# V2b.net
KiCad netlist of a schematic drawn in EAGLE
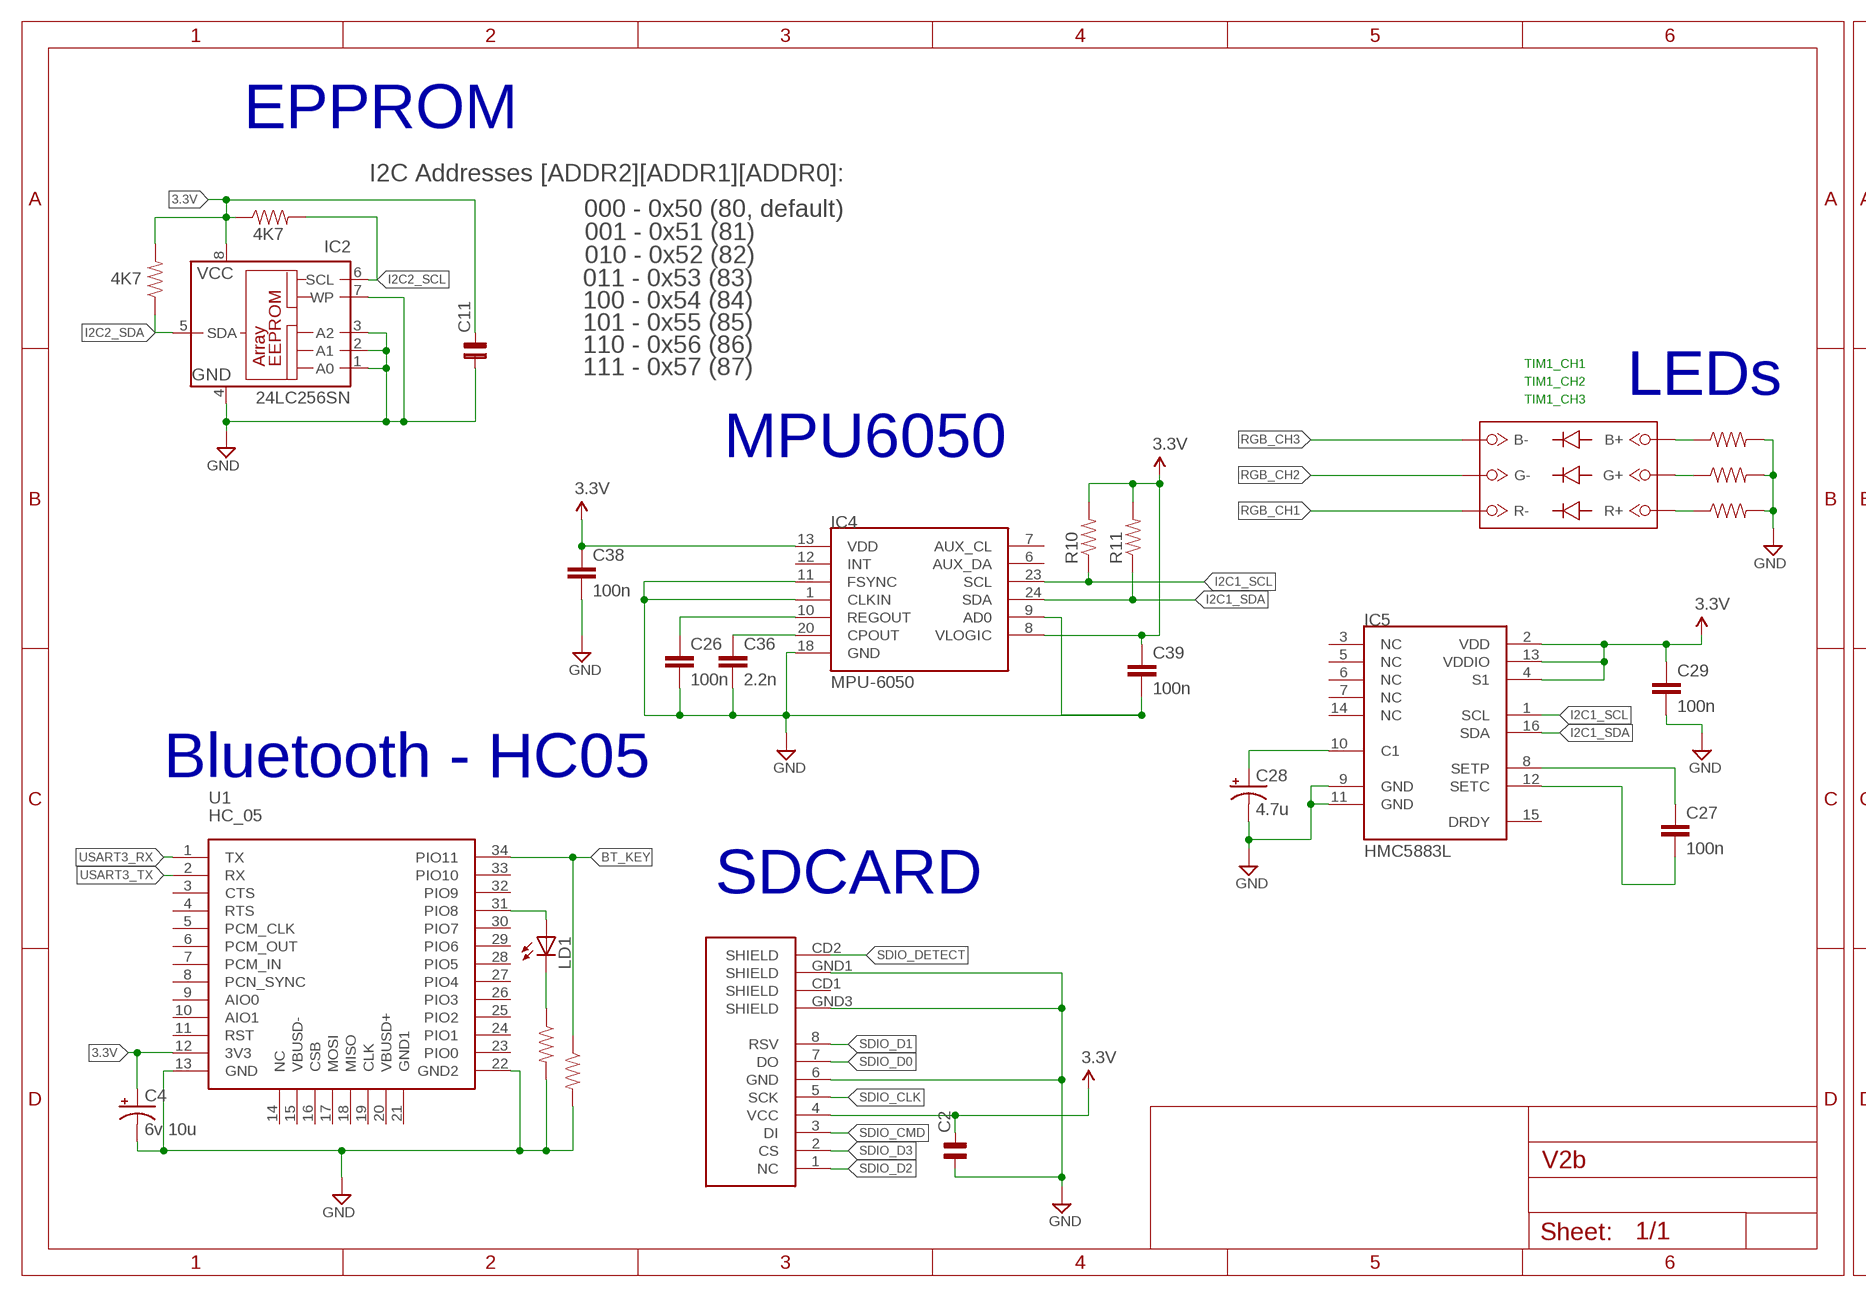
[diagram p0: schematic, sheet 1, part 1 of 2]
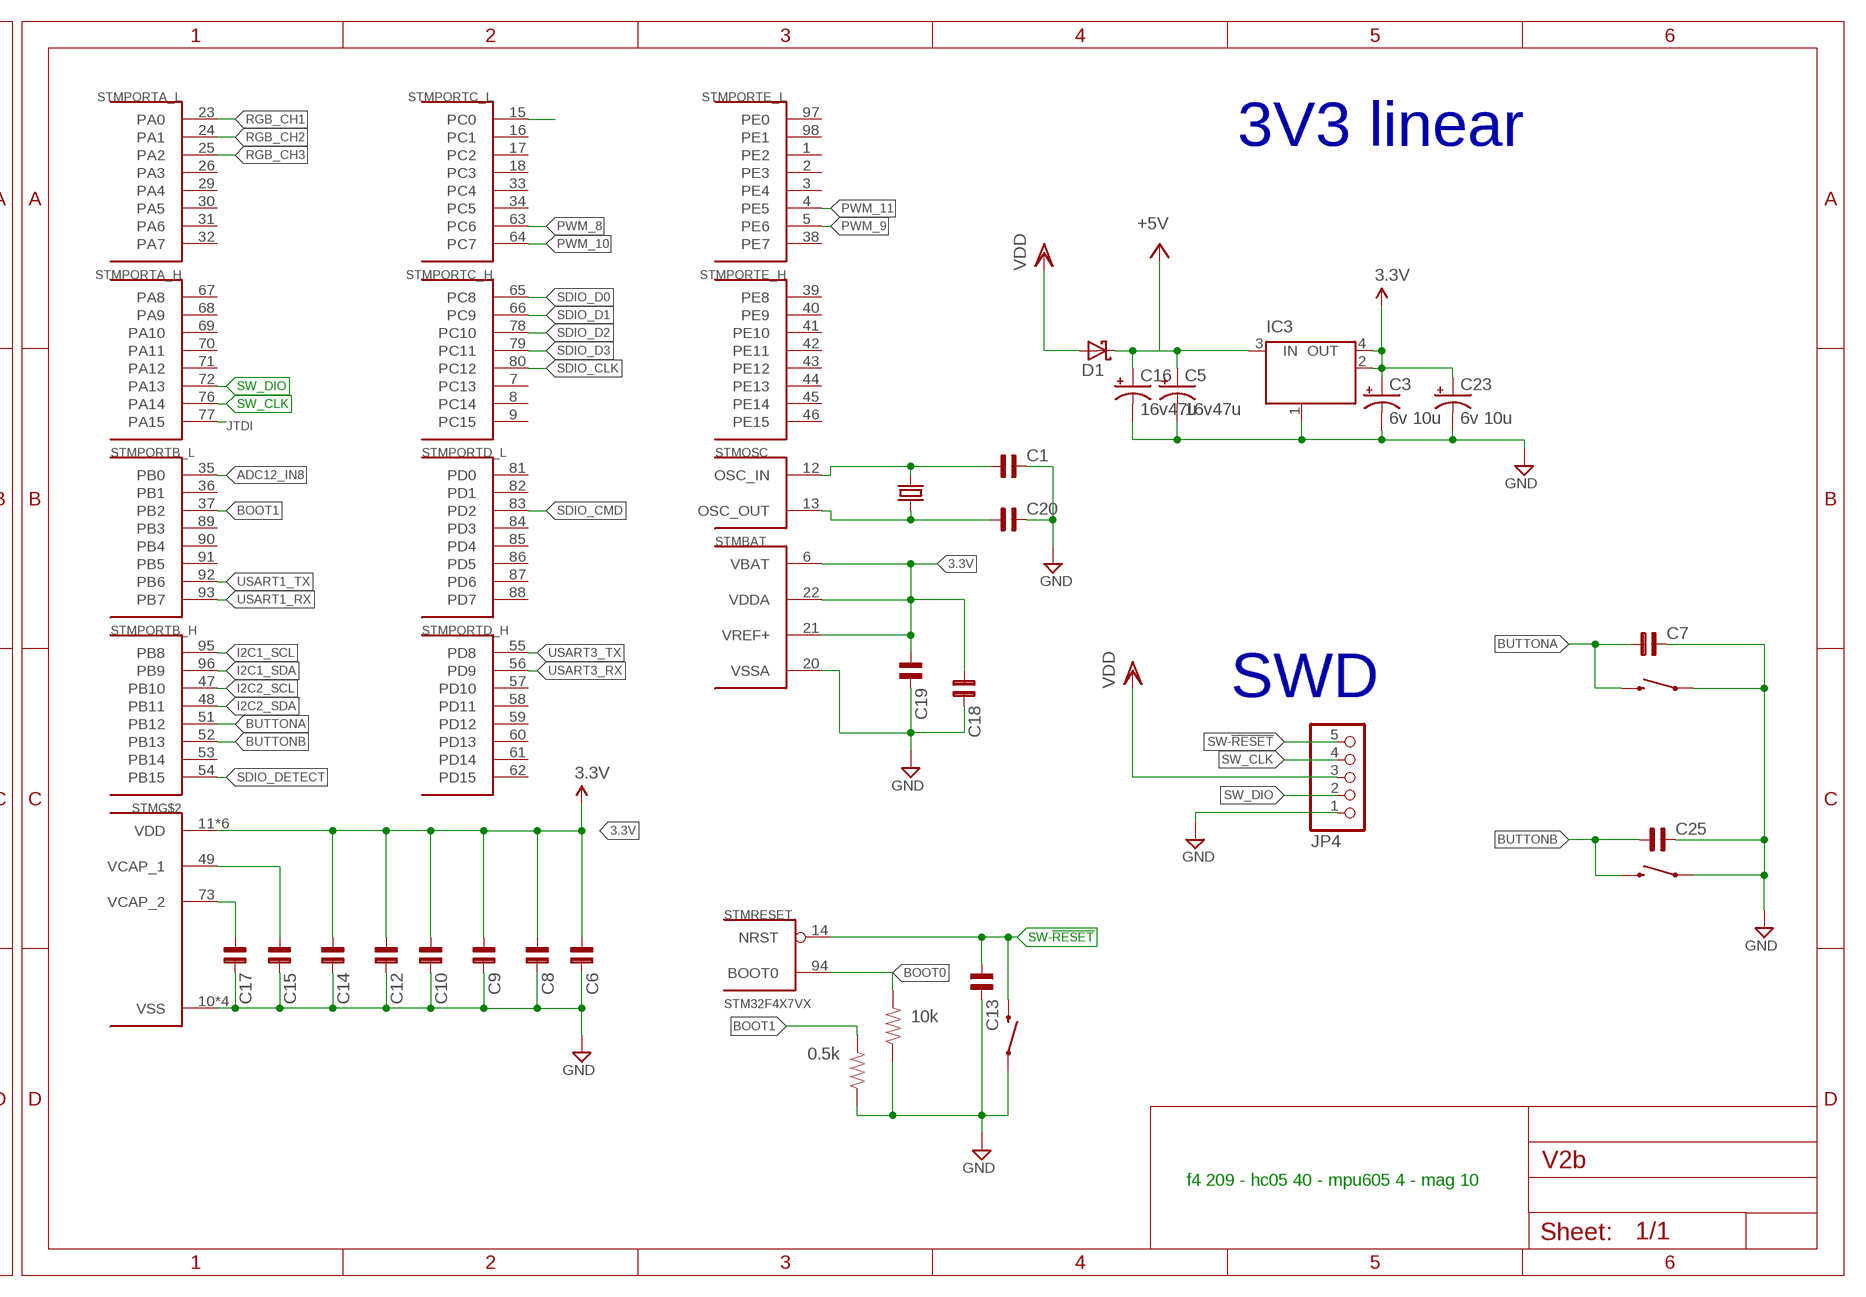
[diagram p1: schematic, sheet 1, part 2 of 2]

(export (version "E")
  (design (tool "Eeschema 10.0.6"))
  (components
    (comp (ref "C1")
      (value "C-NP-SMD-0603")
      (footprint "eagle-import:C-0603")
      (libsource (lib "eagle-import") (part "C-NP-SMD-0603"))
    )
    (comp (ref "C2")
      (value "C-NP-SMD-0603")
      (footprint "eagle-import:C-0603")
      (libsource (lib "eagle-import") (part "C-NP-SMD-0603"))
    )
    (comp (ref "C3")
      (value "6v 10u")
      (footprint "eagle-import:SMC_C")
      (libsource (lib "eagle-import") (part "CPOL-USSMCC"))
    )
    (comp (ref "C4")
      (value "6v 10u")
      (footprint "eagle-import:SMC_A")
      (libsource (lib "eagle-import") (part "CPOL-USSMCA"))
    )
    (comp (ref "C5")
      (value "16v47u")
      (footprint "eagle-import:SMC_C")
      (libsource (lib "eagle-import") (part "CPOL-USSMCC"))
    )
    (comp (ref "C6")
      (value "C-NP-SMD-0603")
      (footprint "eagle-import:C-0603")
      (libsource (lib "eagle-import") (part "C-NP-SMD-0603"))
    )
    (comp (ref "C7")
      (value "C-NP-SMD-0603")
      (footprint "eagle-import:C-0603")
      (libsource (lib "eagle-import") (part "C-NP-SMD-0603"))
    )
    (comp (ref "C8")
      (value "C-NP-SMD-0603")
      (footprint "eagle-import:C-0603")
      (libsource (lib "eagle-import") (part "C-NP-SMD-0603"))
    )
    (comp (ref "C9")
      (value "C-NP-SMD-0603")
      (footprint "eagle-import:C-0603")
      (libsource (lib "eagle-import") (part "C-NP-SMD-0603"))
    )
    (comp (ref "C10")
      (value "C-NP-SMD-0603")
      (footprint "eagle-import:C-0603")
      (libsource (lib "eagle-import") (part "C-NP-SMD-0603"))
    )
    (comp (ref "C11")
      (value "C-NP-SMD-0603")
      (footprint "eagle-import:C-0603")
      (libsource (lib "eagle-import") (part "C-NP-SMD-0603"))
    )
    (comp (ref "C12")
      (value "C-NP-SMD-0603")
      (footprint "eagle-import:C-0603")
      (libsource (lib "eagle-import") (part "C-NP-SMD-0603"))
    )
    (comp (ref "C13")
      (value "C-NP-SMD-0603")
      (footprint "eagle-import:C-0603")
      (libsource (lib "eagle-import") (part "C-NP-SMD-0603"))
    )
    (comp (ref "C14")
      (value "C-NP-SMD-0603")
      (footprint "eagle-import:C-0603")
      (libsource (lib "eagle-import") (part "C-NP-SMD-0603"))
    )
    (comp (ref "C15")
      (value "C-NP-SMD-0603")
      (footprint "eagle-import:C-0603")
      (libsource (lib "eagle-import") (part "C-NP-SMD-0603"))
    )
    (comp (ref "C16")
      (value "16v47u")
      (footprint "eagle-import:SMC_C")
      (libsource (lib "eagle-import") (part "CPOL-USSMCC"))
    )
    (comp (ref "C17")
      (value "C-NP-SMD-0603")
      (footprint "eagle-import:C-0603")
      (libsource (lib "eagle-import") (part "C-NP-SMD-0603"))
    )
    (comp (ref "C18")
      (value "C-NP-SMD-0603")
      (footprint "eagle-import:C-0603")
      (libsource (lib "eagle-import") (part "C-NP-SMD-0603"))
    )
    (comp (ref "C19")
      (value "C-NP-SMD-0603")
      (footprint "eagle-import:C-0603")
      (libsource (lib "eagle-import") (part "C-NP-SMD-0603"))
    )
    (comp (ref "C20")
      (value "C-NP-SMD-0603")
      (footprint "eagle-import:C-0603")
      (libsource (lib "eagle-import") (part "C-NP-SMD-0603"))
    )
    (comp (ref "C23")
      (value "6v 10u")
      (footprint "eagle-import:SMC_C")
      (libsource (lib "eagle-import") (part "CPOL-USSMCC"))
    )
    (comp (ref "C25")
      (value "C-NP-SMD-0603")
      (footprint "eagle-import:C-0603")
      (libsource (lib "eagle-import") (part "C-NP-SMD-0603"))
    )
    (comp (ref "C26")
      (value "100n")
      (footprint "eagle-import:SPARKFUN_0603-CAP")
      (libsource (lib "eagle-import") (part "SPARKFUN_CAP0603-CAP"))
    )
    (comp (ref "C27")
      (value "100n")
      (footprint "eagle-import:SPARKFUN_0603-CAP")
      (libsource (lib "eagle-import") (part "SPARKFUN_CAP0603-CAP"))
    )
    (comp (ref "C28")
      (value "4.7u")
      (footprint "eagle-import:SMC_A")
      (libsource (lib "eagle-import") (part "CPOL-USSMCA"))
    )
    (comp (ref "C29")
      (value "100n")
      (footprint "eagle-import:SPARKFUN_0603-CAP")
      (libsource (lib "eagle-import") (part "SPARKFUN_CAP0603-CAP"))
    )
    (comp (ref "C36")
      (value "2.2n")
      (footprint "eagle-import:SPARKFUN_0603-CAP")
      (libsource (lib "eagle-import") (part "SPARKFUN_CAP0603-CAP"))
    )
    (comp (ref "C38")
      (value "100n")
      (footprint "eagle-import:SPARKFUN_0603-CAP")
      (libsource (lib "eagle-import") (part "SPARKFUN_CAP0603-CAP"))
    )
    (comp (ref "C39")
      (value "100n")
      (footprint "eagle-import:SPARKFUN_0603-CAP")
      (libsource (lib "eagle-import") (part "SPARKFUN_CAP0603-CAP"))
    )
    (comp (ref "D1")
      (value "MBRS330T3")
      (footprint "eagle-import:SMC")
      (libsource (lib "eagle-import") (part "MBRS30T33"))
    )
    (comp (ref "IC2")
      (value "24LC256SN")
      (footprint "eagle-import:SO-08")
      (fields (field (name "MF") "MICROCHIP") (field (name "MPN") "24LC256-I/SN"))
      (libsource (lib "eagle-import") (part "24SNLC256"))
    )
    (comp (ref "IC3")
      (value "LINEAR_MC33269ST-3.3T3")
      (footprint "eagle-import:LINEAR_SOT223")
      (libsource (lib "eagle-import") (part "LINEAR_MC33269ST-3.3T3"))
    )
    (comp (ref "IC4")
      (value "MPU-6050")
      (footprint "eagle-import:TESTING_QFN-24-4MM2")
      (libsource (lib "eagle-import") (part "TESTING_MPU-6050-1"))
    )
    (comp (ref "IC5")
      (value "HMC5883L")
      (footprint "eagle-import:SPARKFUN_16LPCC")
      (libsource (lib "eagle-import") (part "SPARKFUN_HMC5883LSMD"))
    )
    (comp (ref "JP4")
      (value "PINHD-1X5_2.54-90°")
      (footprint "eagle-import:1X05_90")
      (libsource (lib "eagle-import") (part "PINHD-1X5_2.54-90°"))
    )
    (comp (ref "LD1")
      (value "LEDCHIPLED_0603")
      (footprint "eagle-import:CHIPLED_0603")
      (libsource (lib "eagle-import") (part "LEDCHIPLED_0603"))
    )
    (comp (ref "R2")
      (value "10K")
      (footprint "eagle-import:SPARKFUN_0603-RES")
      (libsource (lib "eagle-import") (part "Robotech_RCL_SPARKFUN_RESISTOR0603-RES"))
    )
    (comp (ref "R3")
      (value "10K")
      (footprint "eagle-import:SPARKFUN_0603-RES")
      (libsource (lib "eagle-import") (part "Robotech_RCL_SPARKFUN_RESISTOR0603-RES"))
    )
    (comp (ref "R5")
      (value "10K")
      (footprint "eagle-import:SPARKFUN_0603-RES")
      (libsource (lib "eagle-import") (part "Robotech_RCL_SPARKFUN_RESISTOR0603-RES"))
    )
    (comp (ref "R6")
      (value "10K")
      (footprint "eagle-import:SPARKFUN_0603-RES")
      (libsource (lib "eagle-import") (part "Robotech_RCL_SPARKFUN_RESISTOR0603-RES"))
    )
    (comp (ref "R7")
      (value "10k")
      (footprint "eagle-import:SPARKFUN_0603-RES")
      (libsource (lib "eagle-import") (part "Robotech_RCL_SPARKFUN_RESISTOR0603-RES"))
    )
    (comp (ref "R8")
      (value "0.5k")
      (footprint "eagle-import:SPARKFUN_0603-RES")
      (libsource (lib "eagle-import") (part "Robotech_RCL_SPARKFUN_RESISTOR0603-RES"))
    )
    (comp (ref "R9")
      (value "10K")
      (footprint "eagle-import:SPARKFUN_0603-RES")
      (libsource (lib "eagle-import") (part "Robotech_RCL_SPARKFUN_RESISTOR0603-RES"))
    )
    (comp (ref "R10")
      (value "SPARKFUN_RESISTOR0603-RES")
      (footprint "eagle-import:SPARKFUN_0603-RES")
      (libsource (lib "eagle-import") (part "SPARKFUN_RESISTOR0603-RES"))
    )
    (comp (ref "R11")
      (value "SPARKFUN_RESISTOR0603-RES")
      (footprint "eagle-import:SPARKFUN_0603-RES")
      (libsource (lib "eagle-import") (part "SPARKFUN_RESISTOR0603-RES"))
    )
    (comp (ref "R15")
      (value "4K7")
      (footprint "eagle-import:SPARKFUN_0603-RES")
      (libsource (lib "eagle-import") (part "Robotech_RCL_SPARKFUN_RESISTOR0603-RES"))
    )
    (comp (ref "R16")
      (value "4K7")
      (footprint "eagle-import:SPARKFUN_0603-RES")
      (libsource (lib "eagle-import") (part "Robotech_RCL_SPARKFUN_RESISTOR0603-RES"))
    )
    (comp (ref "S1")
      (value "RESET")
      (footprint "eagle-import:TACTILE-SWITCH-1101NE")
      (fields (field (name "PARTNO") "EVQ-P7J01P"))
      (libsource (lib "eagle-import") (part "SWITCH-MOMENTARY-2-SMD-1101NE"))
    )
    (comp (ref "S2")
      (value "RESET")
      (footprint "eagle-import:TACTILE-SWITCH-1101NE")
      (fields (field (name "PARTNO") "EVQ-P7J01P"))
      (libsource (lib "eagle-import") (part "SWITCH-MOMENTARY-2-SMD-1101NE"))
    )
    (comp (ref "S4")
      (value "RESET")
      (footprint "eagle-import:TACTILE-SWITCH-1101NE")
      (fields (field (name "PARTNO") "EVQ-P7J01P"))
      (libsource (lib "eagle-import") (part "SWITCH-MOMENTARY-2-SMD-1101NE"))
    )
    (comp (ref "SDCARD2")
      (value "microSD Socket")
      (footprint "eagle-import:MICRO-SD-SOCKET-PP")
      (libsource (lib "eagle-import") (part "USD-SOCKETNEW"))
    )
    (comp (ref "STM")
      (value "STM32F4X7VX")
      (footprint "eagle-import:TQFP100")
      (fields (field (name "PARTNO") "STM32F427VI"))
      (libsource (lib "eagle-import") (part "STM32F4X7VX"))
    )
    (comp (ref "U$12")
      (value "RGB_LED")
      (footprint "eagle-import:SMD")
      (libsource (lib "eagle-import") (part "RGB_LED"))
    )
    (comp (ref "U1")
      (value "HC_05")
      (footprint "eagle-import:BLUETOOTH_SMD")
      (libsource (lib "eagle-import") (part "HC_05"))
    )
    (comp (ref "Y1")
      (value "CRYSTALHC49US")
      (footprint "eagle-import:HC49US")
      (libsource (lib "eagle-import") (part "CRYSTALHC49US"))
    )
  )
  (nets
    (net (code "1") (name "+5V") (class "Default")
      (node (ref "C16") (pin "+") (pinfunction "+_+") (pintype "passive"))
      (node (ref "C5") (pin "+") (pinfunction "+_+") (pintype "passive"))
      (node (ref "D1") (pin "C") (pinfunction "C_C") (pintype "passive"))
      (node (ref "IC3") (pin "3") (pinfunction "IN_3") (pintype "input"))
    )
    (net (code "2") (name "/JTDI") (class "Default")
      (node (ref "STM") (pin "77") (pinfunction "PA15_77") (pintype "bidirectional"))
    )
    (net (code "3") (name "/SW-~{RESET}") (class "Default")
      (node (ref "C13") (pin "1") (pinfunction "1_1") (pintype "passive"))
      (node (ref "JP4") (pin "5") (pinfunction "5_5") (pintype "passive"))
      (node (ref "S1") (pin "P$2") (pinfunction "2_P$2") (pintype "passive"))
      (node (ref "STM") (pin "14") (pinfunction "NRST_14") (pintype "input"))
    )
    (net (code "4") (name "3.3V") (class "Default")
      (node (ref "C10") (pin "1") (pinfunction "1_1") (pintype "passive"))
      (node (ref "C11") (pin "2") (pinfunction "2_2") (pintype "passive"))
      (node (ref "C12") (pin "1") (pinfunction "1_1") (pintype "passive"))
      (node (ref "C14") (pin "1") (pinfunction "1_1") (pintype "passive"))
      (node (ref "C18") (pin "1") (pinfunction "1_1") (pintype "passive"))
      (node (ref "C19") (pin "1") (pinfunction "1_1") (pintype "passive"))
      (node (ref "C2") (pin "2") (pinfunction "2_2") (pintype "passive"))
      (node (ref "C23") (pin "+") (pinfunction "+_+") (pintype "passive"))
      (node (ref "C29") (pin "1") (pinfunction "1_1") (pintype "passive"))
      (node (ref "C3") (pin "+") (pinfunction "+_+") (pintype "passive"))
      (node (ref "C38") (pin "1") (pinfunction "1_1") (pintype "passive"))
      (node (ref "C39") (pin "1") (pinfunction "1_1") (pintype "passive"))
      (node (ref "C4") (pin "+") (pinfunction "+_+") (pintype "passive"))
      (node (ref "C6") (pin "1") (pinfunction "1_1") (pintype "passive"))
      (node (ref "C8") (pin "1") (pinfunction "1_1") (pintype "passive"))
      (node (ref "C9") (pin "1") (pinfunction "1_1") (pintype "passive"))
      (node (ref "IC2") (pin "8") (pinfunction "VCC_8") (pintype "power_in"))
      (node (ref "IC3") (pin "2") (pinfunction "OUT_2") (pintype "passive"))
      (node (ref "IC3") (pin "4") (pinfunction "OUT_4") (pintype "passive"))
      (node (ref "IC4") (pin "13") (pinfunction "VDD_13") (pintype "bidirectional"))
      (node (ref "IC4") (pin "8") (pinfunction "VLOGIC_8") (pintype "bidirectional"))
      (node (ref "IC5") (pin "13") (pinfunction "VDDIO_13") (pintype "bidirectional"))
      (node (ref "IC5") (pin "2") (pinfunction "VDD_2") (pintype "bidirectional"))
      (node (ref "IC5") (pin "4") (pinfunction "S1_4") (pintype "bidirectional"))
      (node (ref "R10") (pin "2") (pinfunction "2_2") (pintype "passive"))
      (node (ref "R11") (pin "2") (pinfunction "2_2") (pintype "passive"))
      (node (ref "R15") (pin "1") (pinfunction "1_1") (pintype "passive"))
      (node (ref "R16") (pin "2") (pinfunction "2_2") (pintype "passive"))
      (node (ref "SDCARD2") (pin "4") (pinfunction "VCC_4") (pintype "bidirectional"))
      (node (ref "STM") (pin "100") (pinfunction "VDD_100") (pintype "power_in"))
      (node (ref "STM") (pin "11") (pinfunction "VDD_11") (pintype "power_in"))
      (node (ref "STM") (pin "19") (pinfunction "VDD_19") (pintype "power_in"))
      (node (ref "STM") (pin "21") (pinfunction "VREF+_21") (pintype "input"))
      (node (ref "STM") (pin "22") (pinfunction "VDDA_22") (pintype "power_in"))
      (node (ref "STM") (pin "28") (pinfunction "VDD_28") (pintype "power_in"))
      (node (ref "STM") (pin "50") (pinfunction "VDD_50") (pintype "power_in"))
      (node (ref "STM") (pin "6") (pinfunction "VBAT_6") (pintype "power_in"))
      (node (ref "STM") (pin "75") (pinfunction "VDD_75") (pintype "power_in"))
      (node (ref "U1") (pin "12") (pinfunction "3V3_12") (pintype "bidirectional"))
    )
    (net (code "5") (name "ADC12_IN8") (class "Default")
      (node (ref "STM") (pin "35") (pinfunction "PB0_35") (pintype "bidirectional"))
    )
    (net (code "6") (name "BOOT0") (class "Default")
      (node (ref "R7") (pin "2") (pinfunction "2_2") (pintype "passive"))
      (node (ref "STM") (pin "94") (pinfunction "BOOT0_94") (pintype "input"))
    )
    (net (code "7") (name "BOOT1") (class "Default")
      (node (ref "R8") (pin "2") (pinfunction "2_2") (pintype "passive"))
      (node (ref "STM") (pin "37") (pinfunction "PB2_37") (pintype "bidirectional"))
    )
    (net (code "8") (name "BT_KEY") (class "Default")
      (node (ref "R5") (pin "1") (pinfunction "1_1") (pintype "passive"))
      (node (ref "U1") (pin "34") (pinfunction "PIO11_34") (pintype "bidirectional"))
    )
    (net (code "9") (name "BUTTONA") (class "Default")
      (node (ref "C7") (pin "1") (pinfunction "1_1") (pintype "passive"))
      (node (ref "S4") (pin "P$2") (pinfunction "2_P$2") (pintype "passive"))
      (node (ref "STM") (pin "51") (pinfunction "PB12_51") (pintype "bidirectional"))
    )
    (net (code "10") (name "BUTTONB") (class "Default")
      (node (ref "C25") (pin "1") (pinfunction "1_1") (pintype "passive"))
      (node (ref "S2") (pin "P$2") (pinfunction "2_P$2") (pintype "passive"))
      (node (ref "STM") (pin "52") (pinfunction "PB13_52") (pintype "bidirectional"))
    )
    (net (code "11") (name "GND") (class "Default")
      (node (ref "C1") (pin "2") (pinfunction "2_2") (pintype "passive"))
      (node (ref "C10") (pin "2") (pinfunction "2_2") (pintype "passive"))
      (node (ref "C11") (pin "1") (pinfunction "1_1") (pintype "passive"))
      (node (ref "C12") (pin "2") (pinfunction "2_2") (pintype "passive"))
      (node (ref "C13") (pin "2") (pinfunction "2_2") (pintype "passive"))
      (node (ref "C14") (pin "2") (pinfunction "2_2") (pintype "passive"))
      (node (ref "C15") (pin "2") (pinfunction "2_2") (pintype "passive"))
      (node (ref "C16") (pin "-") (pinfunction "-_-") (pintype "passive"))
      (node (ref "C17") (pin "2") (pinfunction "2_2") (pintype "passive"))
      (node (ref "C18") (pin "2") (pinfunction "2_2") (pintype "passive"))
      (node (ref "C19") (pin "2") (pinfunction "2_2") (pintype "passive"))
      (node (ref "C2") (pin "1") (pinfunction "1_1") (pintype "passive"))
      (node (ref "C20") (pin "2") (pinfunction "2_2") (pintype "passive"))
      (node (ref "C23") (pin "-") (pinfunction "-_-") (pintype "passive"))
      (node (ref "C25") (pin "2") (pinfunction "2_2") (pintype "passive"))
      (node (ref "C26") (pin "2") (pinfunction "2_2") (pintype "passive"))
      (node (ref "C28") (pin "-") (pinfunction "-_-") (pintype "passive"))
      (node (ref "C29") (pin "2") (pinfunction "2_2") (pintype "passive"))
      (node (ref "C3") (pin "-") (pinfunction "-_-") (pintype "passive"))
      (node (ref "C36") (pin "2") (pinfunction "2_2") (pintype "passive"))
      (node (ref "C38") (pin "2") (pinfunction "2_2") (pintype "passive"))
      (node (ref "C39") (pin "2") (pinfunction "2_2") (pintype "passive"))
      (node (ref "C4") (pin "-") (pinfunction "-_-") (pintype "passive"))
      (node (ref "C5") (pin "-") (pinfunction "-_-") (pintype "passive"))
      (node (ref "C6") (pin "2") (pinfunction "2_2") (pintype "passive"))
      (node (ref "C7") (pin "2") (pinfunction "2_2") (pintype "passive"))
      (node (ref "C8") (pin "2") (pinfunction "2_2") (pintype "passive"))
      (node (ref "C9") (pin "2") (pinfunction "2_2") (pintype "passive"))
      (node (ref "IC2") (pin "1") (pinfunction "A0_1") (pintype "input"))
      (node (ref "IC2") (pin "2") (pinfunction "A1_2") (pintype "input"))
      (node (ref "IC2") (pin "3") (pinfunction "A2_3") (pintype "input"))
      (node (ref "IC2") (pin "4") (pinfunction "GND_4") (pintype "power_in"))
      (node (ref "IC2") (pin "7") (pinfunction "WP_7") (pintype "input"))
      (node (ref "IC3") (pin "1") (pinfunction "GND/ADJ_1") (pintype "input"))
      (node (ref "IC4") (pin "1") (pinfunction "CLKIN_1") (pintype "bidirectional"))
      (node (ref "IC4") (pin "11") (pinfunction "FSYNC_11") (pintype "bidirectional"))
      (node (ref "IC4") (pin "18") (pinfunction "GND_18") (pintype "bidirectional"))
      (node (ref "IC4") (pin "9") (pinfunction "AD0_9") (pintype "bidirectional"))
      (node (ref "IC5") (pin "11") (pinfunction "GND_11") (pintype "bidirectional"))
      (node (ref "IC5") (pin "9") (pinfunction "GND_9") (pintype "bidirectional"))
      (node (ref "JP4") (pin "1") (pinfunction "1_1") (pintype "passive"))
      (node (ref "R2") (pin "2") (pinfunction "2_2") (pintype "passive"))
      (node (ref "R3") (pin "2") (pinfunction "2_2") (pintype "passive"))
      (node (ref "R5") (pin "2") (pinfunction "2_2") (pintype "passive"))
      (node (ref "R6") (pin "2") (pinfunction "2_2") (pintype "passive"))
      (node (ref "R7") (pin "1") (pinfunction "1_1") (pintype "passive"))
      (node (ref "R8") (pin "1") (pinfunction "1_1") (pintype "passive"))
      (node (ref "R9") (pin "2") (pinfunction "2_2") (pintype "passive"))
      (node (ref "S1") (pin "P$1") (pinfunction "1_P$1") (pintype "passive"))
      (node (ref "S2") (pin "P$1") (pinfunction "1_P$1") (pintype "passive"))
      (node (ref "S4") (pin "P$1") (pinfunction "1_P$1") (pintype "passive"))
      (node (ref "SDCARD2") (pin "6") (pinfunction "GND_6") (pintype "bidirectional"))
      (node (ref "SDCARD2") (pin "GND1") (pinfunction "SHIELD_GND1") (pintype "bidirectional"))
      (node (ref "SDCARD2") (pin "GND3") (pinfunction "SHIELD_GND3") (pintype "bidirectional"))
      (node (ref "STM") (pin "10") (pinfunction "VSS_10") (pintype "power_in"))
      (node (ref "STM") (pin "20") (pinfunction "VSSA_20") (pintype "power_in"))
      (node (ref "STM") (pin "27") (pinfunction "VSS_27") (pintype "power_in"))
      (node (ref "STM") (pin "74") (pinfunction "VSS_74") (pintype "power_in"))
      (node (ref "STM") (pin "99") (pinfunction "VSS_99") (pintype "power_in"))
      (node (ref "U1") (pin "13") (pinfunction "GND_13") (pintype "bidirectional"))
      (node (ref "U1") (pin "22") (pinfunction "GND2_22") (pintype "bidirectional"))
    )
    (net (code "12") (name "I2C1_SCL") (class "Default")
      (node (ref "IC4") (pin "23") (pinfunction "SCL_23") (pintype "bidirectional"))
      (node (ref "IC5") (pin "1") (pinfunction "SCL_1") (pintype "bidirectional"))
      (node (ref "R10") (pin "1") (pinfunction "1_1") (pintype "passive"))
      (node (ref "STM") (pin "95") (pinfunction "PB8_95") (pintype "bidirectional"))
    )
    (net (code "13") (name "I2C1_SDA") (class "Default")
      (node (ref "IC4") (pin "24") (pinfunction "SDA_24") (pintype "bidirectional"))
      (node (ref "IC5") (pin "16") (pinfunction "SDA_16") (pintype "bidirectional"))
      (node (ref "R11") (pin "1") (pinfunction "1_1") (pintype "passive"))
      (node (ref "STM") (pin "96") (pinfunction "PB9_96") (pintype "bidirectional"))
    )
    (net (code "14") (name "I2C2_SCL") (class "Default")
      (node (ref "IC2") (pin "6") (pinfunction "SCL_6") (pintype "input"))
      (node (ref "R15") (pin "2") (pinfunction "2_2") (pintype "passive"))
      (node (ref "STM") (pin "47") (pinfunction "PB10_47") (pintype "bidirectional"))
    )
    (net (code "15") (name "I2C2_SDA") (class "Default")
      (node (ref "IC2") (pin "5") (pinfunction "SDA_5") (pintype "bidirectional"))
      (node (ref "R16") (pin "1") (pinfunction "1_1") (pintype "passive"))
      (node (ref "STM") (pin "48") (pinfunction "PB11_48") (pintype "bidirectional"))
    )
    (net (code "16") (name "Net-(IC4-CPOUT)") (class "Default")
      (node (ref "C36") (pin "1") (pinfunction "1_1") (pintype "passive"))
      (node (ref "IC4") (pin "20") (pinfunction "CPOUT_20") (pintype "bidirectional"))
    )
    (net (code "17") (name "Net-(IC4-REGOUT)") (class "Default")
      (node (ref "C26") (pin "1") (pinfunction "1_1") (pintype "passive"))
      (node (ref "IC4") (pin "10") (pinfunction "REGOUT_10") (pintype "bidirectional"))
    )
    (net (code "18") (name "Net-(IC5-C1)") (class "Default")
      (node (ref "C28") (pin "+") (pinfunction "+_+") (pintype "passive"))
      (node (ref "IC5") (pin "10") (pinfunction "C1_10") (pintype "bidirectional"))
    )
    (net (code "19") (name "Net-(IC5-SETC)") (class "Default")
      (node (ref "C27") (pin "2") (pinfunction "2_2") (pintype "passive"))
      (node (ref "IC5") (pin "12") (pinfunction "SETC_12") (pintype "bidirectional"))
    )
    (net (code "20") (name "Net-(IC5-SETP)") (class "Default")
      (node (ref "C27") (pin "1") (pinfunction "1_1") (pintype "passive"))
      (node (ref "IC5") (pin "8") (pinfunction "SETP_8") (pintype "bidirectional"))
    )
    (net (code "21") (name "Net-(LD1-PadC)") (class "Default")
      (node (ref "LD1") (pin "C") (pinfunction "C_C") (pintype "passive"))
      (node (ref "R9") (pin "1") (pinfunction "1_1") (pintype "passive"))
    )
    (net (code "22") (name "Net-(R2-Pad1)") (class "Default")
      (node (ref "R2") (pin "1") (pinfunction "1_1") (pintype "passive"))
      (node (ref "U$12") (pin "B+") (pinfunction "B+_B+") (pintype "bidirectional"))
    )
    (net (code "23") (name "Net-(R3-Pad1)") (class "Default")
      (node (ref "R3") (pin "1") (pinfunction "1_1") (pintype "passive"))
      (node (ref "U$12") (pin "G+") (pinfunction "G+_G+") (pintype "bidirectional"))
    )
    (net (code "24") (name "Net-(R6-Pad1)") (class "Default")
      (node (ref "R6") (pin "1") (pinfunction "1_1") (pintype "passive"))
      (node (ref "U$12") (pin "R+") (pinfunction "R+_R+") (pintype "bidirectional"))
    )
    (net (code "25") (name "Net-(STMB-VCAP_1)") (class "Default")
      (node (ref "C15") (pin "1") (pinfunction "1_1") (pintype "passive"))
      (node (ref "STM") (pin "49") (pinfunction "VCAP_1_49") (pintype "power_in"))
    )
    (net (code "26") (name "Net-(STMB-VCAP_2)") (class "Default")
      (node (ref "C17") (pin "1") (pinfunction "1_1") (pintype "passive"))
      (node (ref "STM") (pin "73") (pinfunction "VCAP_2_73") (pintype "power_in"))
    )
    (net (code "27") (name "Net-(STMC-OSC_IN)") (class "Default")
      (node (ref "C1") (pin "1") (pinfunction "1_1") (pintype "passive"))
      (node (ref "STM") (pin "12") (pinfunction "OSC_IN_12") (pintype "input"))
      (node (ref "Y1") (pin "2") (pinfunction "2_2") (pintype "passive"))
    )
    (net (code "28") (name "Net-(STMC-OSC_OUT)") (class "Default")
      (node (ref "C20") (pin "1") (pinfunction "1_1") (pintype "passive"))
      (node (ref "STM") (pin "13") (pinfunction "OSC_OUT_13") (pintype "output"))
      (node (ref "Y1") (pin "1") (pinfunction "1_1") (pintype "passive"))
    )
    (net (code "29") (name "Net-(U1-PIO8)") (class "Default")
      (node (ref "LD1") (pin "A") (pinfunction "A_A") (pintype "passive"))
      (node (ref "U1") (pin "31") (pinfunction "PIO8_31") (pintype "bidirectional"))
    )
    (net (code "30") (name "PWM_8") (class "Default")
      (node (ref "STM") (pin "63") (pinfunction "PC6_63") (pintype "bidirectional"))
    )
    (net (code "31") (name "PWM_9") (class "Default")
      (node (ref "STM") (pin "5") (pinfunction "PE6_5") (pintype "bidirectional"))
    )
    (net (code "32") (name "PWM_10") (class "Default")
      (node (ref "STM") (pin "64") (pinfunction "PC7_64") (pintype "bidirectional"))
    )
    (net (code "33") (name "PWM_11") (class "Default")
      (node (ref "STM") (pin "4") (pinfunction "PE5_4") (pintype "bidirectional"))
    )
    (net (code "34") (name "RGB_CH1") (class "Default")
      (node (ref "STM") (pin "23") (pinfunction "PA0_23") (pintype "bidirectional"))
      (node (ref "U$12") (pin "R-") (pinfunction "R-_R-") (pintype "bidirectional"))
    )
    (net (code "35") (name "RGB_CH2") (class "Default")
      (node (ref "STM") (pin "24") (pinfunction "PA1_24") (pintype "bidirectional"))
      (node (ref "U$12") (pin "G-") (pinfunction "G-_G-") (pintype "bidirectional"))
    )
    (net (code "36") (name "RGB_CH3") (class "Default")
      (node (ref "STM") (pin "25") (pinfunction "PA2_25") (pintype "bidirectional"))
      (node (ref "U$12") (pin "B-") (pinfunction "B-_B-") (pintype "bidirectional"))
    )
    (net (code "37") (name "SDIO_CLK") (class "Default")
      (node (ref "SDCARD2") (pin "5") (pinfunction "SCK_5") (pintype "bidirectional"))
      (node (ref "STM") (pin "80") (pinfunction "PC12_80") (pintype "bidirectional"))
    )
    (net (code "38") (name "SDIO_CMD") (class "Default")
      (node (ref "SDCARD2") (pin "3") (pinfunction "DI_3") (pintype "bidirectional"))
      (node (ref "STM") (pin "83") (pinfunction "PD2_83") (pintype "bidirectional"))
    )
    (net (code "39") (name "SDIO_D0") (class "Default")
      (node (ref "SDCARD2") (pin "7") (pinfunction "DO_7") (pintype "bidirectional"))
      (node (ref "STM") (pin "65") (pinfunction "PC8_65") (pintype "bidirectional"))
    )
    (net (code "40") (name "SDIO_D1") (class "Default")
      (node (ref "SDCARD2") (pin "8") (pinfunction "RSV_8") (pintype "bidirectional"))
      (node (ref "STM") (pin "66") (pinfunction "PC9_66") (pintype "bidirectional"))
    )
    (net (code "41") (name "SDIO_D2") (class "Default")
      (node (ref "SDCARD2") (pin "1") (pinfunction "NC_1") (pintype "bidirectional"))
      (node (ref "STM") (pin "78") (pinfunction "PC10_78") (pintype "bidirectional"))
    )
    (net (code "42") (name "SDIO_D3") (class "Default")
      (node (ref "SDCARD2") (pin "2") (pinfunction "CS_2") (pintype "bidirectional"))
      (node (ref "STM") (pin "79") (pinfunction "PC11_79") (pintype "bidirectional"))
    )
    (net (code "43") (name "SDIO_DETECT") (class "Default")
      (node (ref "SDCARD2") (pin "CD2") (pinfunction "SHIELD_CD2") (pintype "bidirectional"))
      (node (ref "STM") (pin "54") (pinfunction "PB15_54") (pintype "bidirectional"))
    )
    (net (code "44") (name "SW_CLK") (class "Default")
      (node (ref "JP4") (pin "4") (pinfunction "4_4") (pintype "passive"))
      (node (ref "STM") (pin "76") (pinfunction "PA14_76") (pintype "bidirectional"))
    )
    (net (code "45") (name "SW_DIO") (class "Default")
      (node (ref "JP4") (pin "2") (pinfunction "2_2") (pintype "passive"))
      (node (ref "STM") (pin "72") (pinfunction "PA13_72") (pintype "bidirectional"))
    )
    (net (code "46") (name "USART1_RX") (class "Default")
      (node (ref "STM") (pin "93") (pinfunction "PB7_93") (pintype "bidirectional"))
    )
    (net (code "47") (name "USART1_TX") (class "Default")
      (node (ref "STM") (pin "92") (pinfunction "PB6_92") (pintype "bidirectional"))
    )
    (net (code "48") (name "USART3_RX") (class "Default")
      (node (ref "STM") (pin "56") (pinfunction "PD9_56") (pintype "bidirectional"))
      (node (ref "U1") (pin "1") (pinfunction "TX_1") (pintype "bidirectional"))
    )
    (net (code "49") (name "USART3_TX") (class "Default")
      (node (ref "STM") (pin "55") (pinfunction "PD8_55") (pintype "bidirectional"))
      (node (ref "U1") (pin "2") (pinfunction "RX_2") (pintype "bidirectional"))
    )
    (net (code "50") (name "VDD") (class "Default")
      (node (ref "D1") (pin "A") (pinfunction "A_A") (pintype "passive"))
      (node (ref "JP4") (pin "3") (pinfunction "3_3") (pintype "passive"))
    )
    (net (code "51") (name "unconnected-(IC4-AUX_CL-Pad7)") (class "Default")
      (node (ref "IC4") (pin "7") (pinfunction "AUX_CL_7") (pintype "bidirectional"))
    )
    (net (code "52") (name "unconnected-(IC4-AUX_DA-Pad6)") (class "Default")
      (node (ref "IC4") (pin "6") (pinfunction "AUX_DA_6") (pintype "bidirectional"))
    )
    (net (code "53") (name "unconnected-(IC4-INT-Pad12)") (class "Default")
      (node (ref "IC4") (pin "12") (pinfunction "INT_12") (pintype "bidirectional"))
    )
    (net (code "54") (name "unconnected-(IC5-DRDY-Pad15)") (class "Default")
      (node (ref "IC5") (pin "15") (pinfunction "DRDY_15") (pintype "bidirectional"))
    )
    (net (code "55") (name "unconnected-(IC5-NC-Pad3)") (class "Default")
      (node (ref "IC5") (pin "3") (pinfunction "NC_3") (pintype "bidirectional"))
    )
    (net (code "56") (name "unconnected-(IC5-NC-Pad5)") (class "Default")
      (node (ref "IC5") (pin "5") (pinfunction "NC_5") (pintype "bidirectional"))
    )
    (net (code "57") (name "unconnected-(IC5-NC-Pad6)") (class "Default")
      (node (ref "IC5") (pin "6") (pinfunction "NC_6") (pintype "bidirectional"))
    )
    (net (code "58") (name "unconnected-(IC5-NC-Pad7)") (class "Default")
      (node (ref "IC5") (pin "7") (pinfunction "NC_7") (pintype "bidirectional"))
    )
    (net (code "59") (name "unconnected-(IC5-NC-Pad14)") (class "Default")
      (node (ref "IC5") (pin "14") (pinfunction "NC_14") (pintype "bidirectional"))
    )
    (net (code "60") (name "unconnected-(SDCARD2-SHIELD-PadCD1)") (class "Default")
      (node (ref "SDCARD2") (pin "CD1") (pinfunction "SHIELD_CD1") (pintype "bidirectional"))
    )
    (net (code "61") (name "unconnected-(STMD-PA8-Pad67)") (class "Default")
      (node (ref "STM") (pin "67") (pinfunction "PA8_67") (pintype "bidirectional"))
    )
    (net (code "62") (name "unconnected-(STMD-PA9-Pad68)") (class "Default")
      (node (ref "STM") (pin "68") (pinfunction "PA9_68") (pintype "bidirectional"))
    )
    (net (code "63") (name "unconnected-(STMD-PA10-Pad69)") (class "Default")
      (node (ref "STM") (pin "69") (pinfunction "PA10_69") (pintype "bidirectional"))
    )
    (net (code "64") (name "unconnected-(STMD-PA11-Pad70)") (class "Default")
      (node (ref "STM") (pin "70") (pinfunction "PA11_70") (pintype "bidirectional"))
    )
    (net (code "65") (name "unconnected-(STMD-PA12-Pad71)") (class "Default")
      (node (ref "STM") (pin "71") (pinfunction "PA12_71") (pintype "bidirectional"))
    )
    (net (code "66") (name "unconnected-(STME-PA3-Pad26)") (class "Default")
      (node (ref "STM") (pin "26") (pinfunction "PA3_26") (pintype "bidirectional"))
    )
    (net (code "67") (name "unconnected-(STME-PA4-Pad29)") (class "Default")
      (node (ref "STM") (pin "29") (pinfunction "PA4_29") (pintype "bidirectional"))
    )
    (net (code "68") (name "unconnected-(STME-PA5-Pad30)") (class "Default")
      (node (ref "STM") (pin "30") (pinfunction "PA5_30") (pintype "bidirectional"))
    )
    (net (code "69") (name "unconnected-(STME-PA6-Pad31)") (class "Default")
      (node (ref "STM") (pin "31") (pinfunction "PA6_31") (pintype "bidirectional"))
    )
    (net (code "70") (name "unconnected-(STME-PA7-Pad32)") (class "Default")
      (node (ref "STM") (pin "32") (pinfunction "PA7_32") (pintype "bidirectional"))
    )
    (net (code "71") (name "unconnected-(STMF-PB14-Pad53)") (class "Default")
      (node (ref "STM") (pin "53") (pinfunction "PB14_53") (pintype "bidirectional"))
    )
    (net (code "72") (name "unconnected-(STMG-PB1-Pad36)") (class "Default")
      (node (ref "STM") (pin "36") (pinfunction "PB1_36") (pintype "bidirectional"))
    )
    (net (code "73") (name "unconnected-(STMG-PB3-Pad89)") (class "Default")
      (node (ref "STM") (pin "89") (pinfunction "PB3_89") (pintype "bidirectional"))
    )
    (net (code "74") (name "unconnected-(STMG-PB4-Pad90)") (class "Default")
      (node (ref "STM") (pin "90") (pinfunction "PB4_90") (pintype "bidirectional"))
    )
    (net (code "75") (name "unconnected-(STMG-PB5-Pad91)") (class "Default")
      (node (ref "STM") (pin "91") (pinfunction "PB5_91") (pintype "bidirectional"))
    )
    (net (code "76") (name "unconnected-(STMH-PC13-Pad7)") (class "Default")
      (node (ref "STM") (pin "7") (pinfunction "PC13_7") (pintype "bidirectional"))
    )
    (net (code "77") (name "unconnected-(STMH-PC14-Pad8)") (class "Default")
      (node (ref "STM") (pin "8") (pinfunction "PC14_8") (pintype "bidirectional"))
    )
    (net (code "78") (name "unconnected-(STMH-PC15-Pad9)") (class "Default")
      (node (ref "STM") (pin "9") (pinfunction "PC15_9") (pintype "bidirectional"))
    )
    (net (code "79") (name "unconnected-(STMI-PC0-Pad15)") (class "Default")
      (node (ref "STM") (pin "15") (pinfunction "PC0_15") (pintype "bidirectional"))
    )
    (net (code "80") (name "unconnected-(STMI-PC1-Pad16)") (class "Default")
      (node (ref "STM") (pin "16") (pinfunction "PC1_16") (pintype "bidirectional"))
    )
    (net (code "81") (name "unconnected-(STMI-PC2-Pad17)") (class "Default")
      (node (ref "STM") (pin "17") (pinfunction "PC2_17") (pintype "bidirectional"))
    )
    (net (code "82") (name "unconnected-(STMI-PC3-Pad18)") (class "Default")
      (node (ref "STM") (pin "18") (pinfunction "PC3_18") (pintype "bidirectional"))
    )
    (net (code "83") (name "unconnected-(STMI-PC4-Pad33)") (class "Default")
      (node (ref "STM") (pin "33") (pinfunction "PC4_33") (pintype "bidirectional"))
    )
    (net (code "84") (name "unconnected-(STMI-PC5-Pad34)") (class "Default")
      (node (ref "STM") (pin "34") (pinfunction "PC5_34") (pintype "bidirectional"))
    )
    (net (code "85") (name "unconnected-(STMJ-PD10-Pad57)") (class "Default")
      (node (ref "STM") (pin "57") (pinfunction "PD10_57") (pintype "bidirectional"))
    )
    (net (code "86") (name "unconnected-(STMJ-PD11-Pad58)") (class "Default")
      (node (ref "STM") (pin "58") (pinfunction "PD11_58") (pintype "bidirectional"))
    )
    (net (code "87") (name "unconnected-(STMJ-PD12-Pad59)") (class "Default")
      (node (ref "STM") (pin "59") (pinfunction "PD12_59") (pintype "bidirectional"))
    )
    (net (code "88") (name "unconnected-(STMJ-PD13-Pad60)") (class "Default")
      (node (ref "STM") (pin "60") (pinfunction "PD13_60") (pintype "bidirectional"))
    )
    (net (code "89") (name "unconnected-(STMJ-PD14-Pad61)") (class "Default")
      (node (ref "STM") (pin "61") (pinfunction "PD14_61") (pintype "bidirectional"))
    )
    (net (code "90") (name "unconnected-(STMJ-PD15-Pad62)") (class "Default")
      (node (ref "STM") (pin "62") (pinfunction "PD15_62") (pintype "bidirectional"))
    )
    (net (code "91") (name "unconnected-(STMK-PD0-Pad81)") (class "Default")
      (node (ref "STM") (pin "81") (pinfunction "PD0_81") (pintype "bidirectional"))
    )
    (net (code "92") (name "unconnected-(STMK-PD1-Pad82)") (class "Default")
      (node (ref "STM") (pin "82") (pinfunction "PD1_82") (pintype "bidirectional"))
    )
    (net (code "93") (name "unconnected-(STMK-PD3-Pad84)") (class "Default")
      (node (ref "STM") (pin "84") (pinfunction "PD3_84") (pintype "bidirectional"))
    )
    (net (code "94") (name "unconnected-(STMK-PD4-Pad85)") (class "Default")
      (node (ref "STM") (pin "85") (pinfunction "PD4_85") (pintype "bidirectional"))
    )
    (net (code "95") (name "unconnected-(STMK-PD5-Pad86)") (class "Default")
      (node (ref "STM") (pin "86") (pinfunction "PD5_86") (pintype "bidirectional"))
    )
    (net (code "96") (name "unconnected-(STMK-PD6-Pad87)") (class "Default")
      (node (ref "STM") (pin "87") (pinfunction "PD6_87") (pintype "bidirectional"))
    )
    (net (code "97") (name "unconnected-(STMK-PD7-Pad88)") (class "Default")
      (node (ref "STM") (pin "88") (pinfunction "PD7_88") (pintype "bidirectional"))
    )
    (net (code "98") (name "unconnected-(STML-PE8-Pad39)") (class "Default")
      (node (ref "STM") (pin "39") (pinfunction "PE8_39") (pintype "bidirectional"))
    )
    (net (code "99") (name "unconnected-(STML-PE9-Pad40)") (class "Default")
      (node (ref "STM") (pin "40") (pinfunction "PE9_40") (pintype "bidirectional"))
    )
    (net (code "100") (name "unconnected-(STML-PE10-Pad41)") (class "Default")
      (node (ref "STM") (pin "41") (pinfunction "PE10_41") (pintype "bidirectional"))
    )
    (net (code "101") (name "unconnected-(STML-PE11-Pad42)") (class "Default")
      (node (ref "STM") (pin "42") (pinfunction "PE11_42") (pintype "bidirectional"))
    )
    (net (code "102") (name "unconnected-(STML-PE12-Pad43)") (class "Default")
      (node (ref "STM") (pin "43") (pinfunction "PE12_43") (pintype "bidirectional"))
    )
    (net (code "103") (name "unconnected-(STML-PE13-Pad44)") (class "Default")
      (node (ref "STM") (pin "44") (pinfunction "PE13_44") (pintype "bidirectional"))
    )
    (net (code "104") (name "unconnected-(STML-PE14-Pad45)") (class "Default")
      (node (ref "STM") (pin "45") (pinfunction "PE14_45") (pintype "bidirectional"))
    )
    (net (code "105") (name "unconnected-(STML-PE15-Pad46)") (class "Default")
      (node (ref "STM") (pin "46") (pinfunction "PE15_46") (pintype "bidirectional"))
    )
    (net (code "106") (name "unconnected-(STMM-PE0-Pad97)") (class "Default")
      (node (ref "STM") (pin "97") (pinfunction "PE0_97") (pintype "bidirectional"))
    )
    (net (code "107") (name "unconnected-(STMM-PE1-Pad98)") (class "Default")
      (node (ref "STM") (pin "98") (pinfunction "PE1_98") (pintype "bidirectional"))
    )
    (net (code "108") (name "unconnected-(STMM-PE2-Pad1)") (class "Default")
      (node (ref "STM") (pin "1") (pinfunction "PE2_1") (pintype "bidirectional"))
    )
    (net (code "109") (name "unconnected-(STMM-PE3-Pad2)") (class "Default")
      (node (ref "STM") (pin "2") (pinfunction "PE3_2") (pintype "bidirectional"))
    )
    (net (code "110") (name "unconnected-(STMM-PE4-Pad3)") (class "Default")
      (node (ref "STM") (pin "3") (pinfunction "PE4_3") (pintype "bidirectional"))
    )
    (net (code "111") (name "unconnected-(STMM-PE7-Pad38)") (class "Default")
      (node (ref "STM") (pin "38") (pinfunction "PE7_38") (pintype "bidirectional"))
    )
    (net (code "112") (name "unconnected-(U1-AIO0-Pad9)") (class "Default")
      (node (ref "U1") (pin "9") (pinfunction "AIO0_9") (pintype "bidirectional"))
    )
    (net (code "113") (name "unconnected-(U1-AIO1-Pad10)") (class "Default")
      (node (ref "U1") (pin "10") (pinfunction "AIO1_10") (pintype "bidirectional"))
    )
    (net (code "114") (name "unconnected-(U1-CLK-Pad19)") (class "Default")
      (node (ref "U1") (pin "19") (pinfunction "CLK_19") (pintype "bidirectional"))
    )
    (net (code "115") (name "unconnected-(U1-CSB-Pad16)") (class "Default")
      (node (ref "U1") (pin "16") (pinfunction "CSB_16") (pintype "bidirectional"))
    )
    (net (code "116") (name "unconnected-(U1-CTS-Pad3)") (class "Default")
      (node (ref "U1") (pin "3") (pinfunction "CTS_3") (pintype "bidirectional"))
    )
    (net (code "117") (name "unconnected-(U1-GND1-Pad21)") (class "Default")
      (node (ref "U1") (pin "21") (pinfunction "GND1_21") (pintype "bidirectional"))
    )
    (net (code "118") (name "unconnected-(U1-MISO-Pad18)") (class "Default")
      (node (ref "U1") (pin "18") (pinfunction "MISO_18") (pintype "bidirectional"))
    )
    (net (code "119") (name "unconnected-(U1-MOSI-Pad17)") (class "Default")
      (node (ref "U1") (pin "17") (pinfunction "MOSI_17") (pintype "bidirectional"))
    )
    (net (code "120") (name "unconnected-(U1-NC-Pad14)") (class "Default")
      (node (ref "U1") (pin "14") (pinfunction "NC_14") (pintype "bidirectional"))
    )
    (net (code "121") (name "unconnected-(U1-PCM_CLK-Pad5)") (class "Default")
      (node (ref "U1") (pin "5") (pinfunction "PCM_CLK_5") (pintype "bidirectional"))
    )
    (net (code "122") (name "unconnected-(U1-PCM_IN-Pad7)") (class "Default")
      (node (ref "U1") (pin "7") (pinfunction "PCM_IN_7") (pintype "bidirectional"))
    )
    (net (code "123") (name "unconnected-(U1-PCM_OUT-Pad6)") (class "Default")
      (node (ref "U1") (pin "6") (pinfunction "PCM_OUT_6") (pintype "bidirectional"))
    )
    (net (code "124") (name "unconnected-(U1-PCN_SYNC-Pad8)") (class "Default")
      (node (ref "U1") (pin "8") (pinfunction "PCN_SYNC_8") (pintype "bidirectional"))
    )
    (net (code "125") (name "unconnected-(U1-PIO0-Pad23)") (class "Default")
      (node (ref "U1") (pin "23") (pinfunction "PIO0_23") (pintype "bidirectional"))
    )
    (net (code "126") (name "unconnected-(U1-PIO1-Pad24)") (class "Default")
      (node (ref "U1") (pin "24") (pinfunction "PIO1_24") (pintype "bidirectional"))
    )
    (net (code "127") (name "unconnected-(U1-PIO2-Pad25)") (class "Default")
      (node (ref "U1") (pin "25") (pinfunction "PIO2_25") (pintype "bidirectional"))
    )
    (net (code "128") (name "unconnected-(U1-PIO3-Pad26)") (class "Default")
      (node (ref "U1") (pin "26") (pinfunction "PIO3_26") (pintype "bidirectional"))
    )
    (net (code "129") (name "unconnected-(U1-PIO4-Pad27)") (class "Default")
      (node (ref "U1") (pin "27") (pinfunction "PIO4_27") (pintype "bidirectional"))
    )
    (net (code "130") (name "unconnected-(U1-PIO5-Pad28)") (class "Default")
      (node (ref "U1") (pin "28") (pinfunction "PIO5_28") (pintype "bidirectional"))
    )
    (net (code "131") (name "unconnected-(U1-PIO6-Pad29)") (class "Default")
      (node (ref "U1") (pin "29") (pinfunction "PIO6_29") (pintype "bidirectional"))
    )
    (net (code "132") (name "unconnected-(U1-PIO7-Pad30)") (class "Default")
      (node (ref "U1") (pin "30") (pinfunction "PIO7_30") (pintype "bidirectional"))
    )
    (net (code "133") (name "unconnected-(U1-PIO9-Pad32)") (class "Default")
      (node (ref "U1") (pin "32") (pinfunction "PIO9_32") (pintype "bidirectional"))
    )
    (net (code "134") (name "unconnected-(U1-PIO10-Pad33)") (class "Default")
      (node (ref "U1") (pin "33") (pinfunction "PIO10_33") (pintype "bidirectional"))
    )
    (net (code "135") (name "unconnected-(U1-RST-Pad11)") (class "Default")
      (node (ref "U1") (pin "11") (pinfunction "RST_11") (pintype "bidirectional"))
    )
    (net (code "136") (name "unconnected-(U1-RTS-Pad4)") (class "Default")
      (node (ref "U1") (pin "4") (pinfunction "RTS_4") (pintype "bidirectional"))
    )
    (net (code "137") (name "unconnected-(U1-VBUSD+-Pad20)") (class "Default")
      (node (ref "U1") (pin "20") (pinfunction "VBUSD+_20") (pintype "bidirectional"))
    )
    (net (code "138") (name "unconnected-(U1-VBUSD--Pad15)") (class "Default")
      (node (ref "U1") (pin "15") (pinfunction "VBUSD-_15") (pintype "bidirectional"))
    )
  )
)
